# MyPi.net
KiCad netlist of a schematic drawn in EAGLE
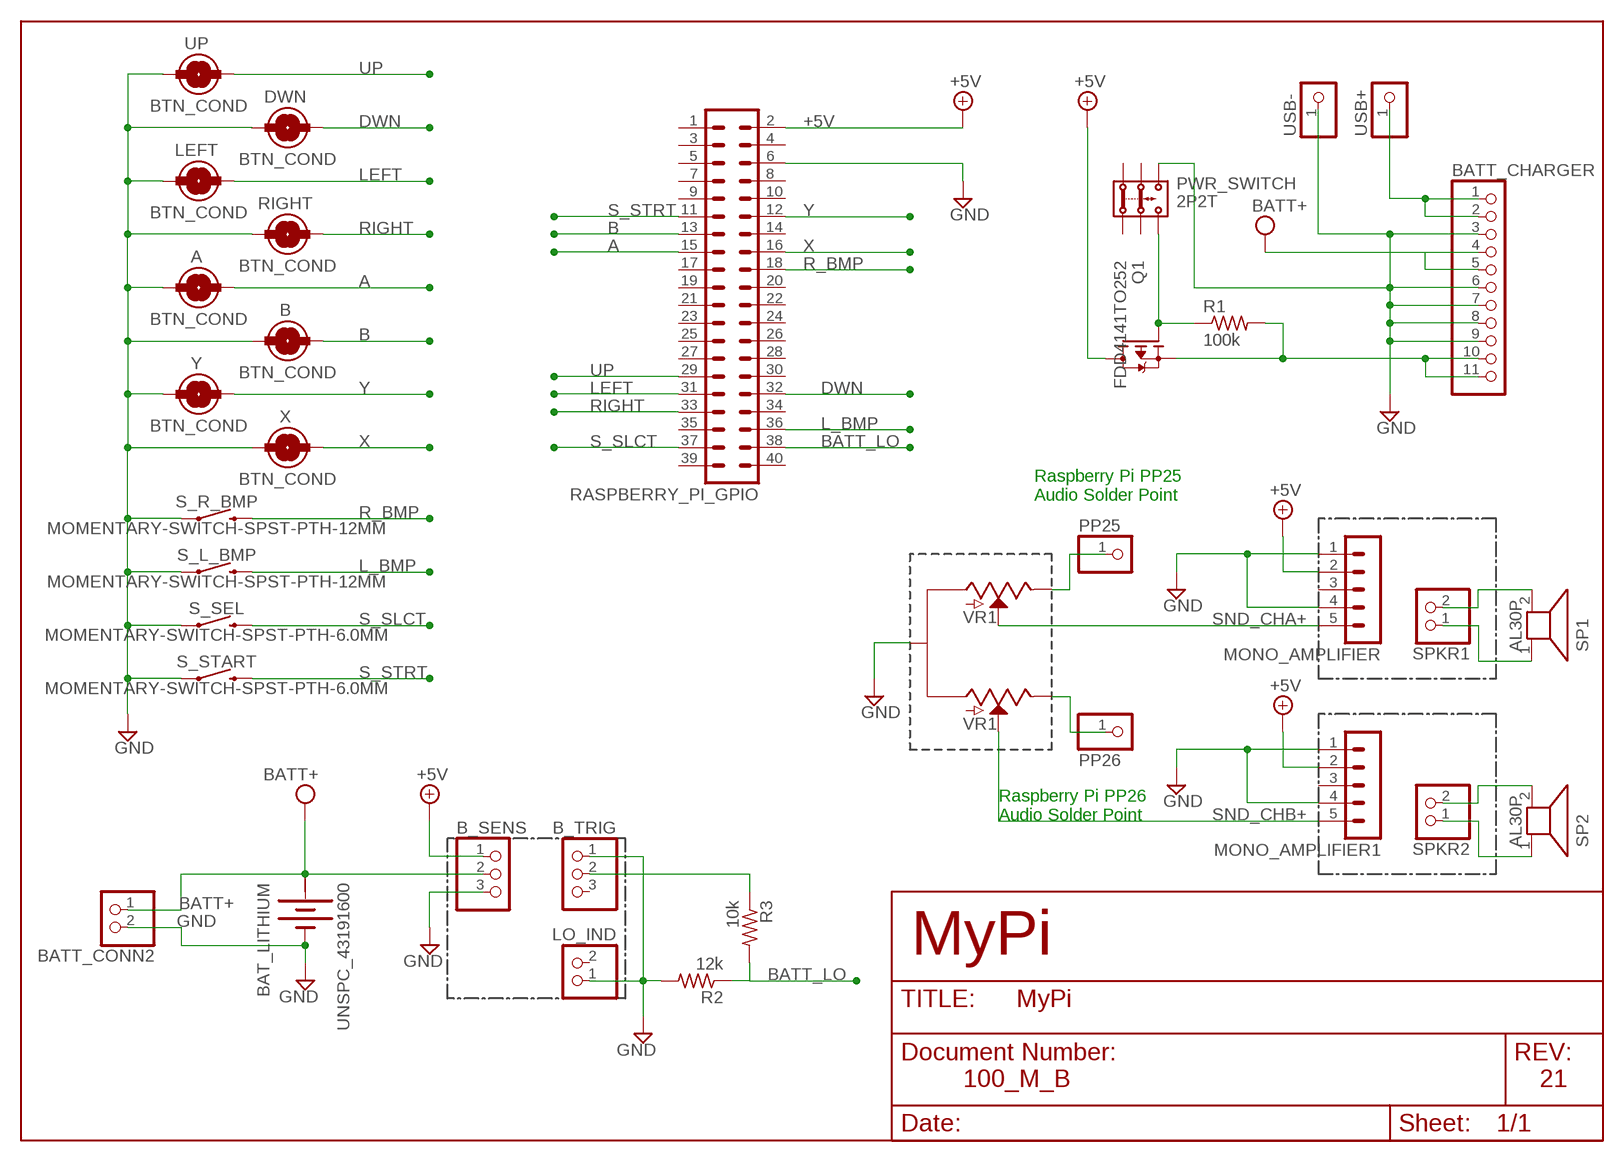
[diagram p0: schematic, sheet 1]

(export (version "E")
  (design (tool "Eeschema 10.0.6"))
  (components
    (comp (ref "A")
      (value "BTN_COND")
      (footprint "eagle-import:BUTTON-CONDUCTIVE-GC")
      (libsource (lib "eagle-import") (part "BTN_COND"))
    )
    (comp (ref "B")
      (value "BTN_COND")
      (footprint "eagle-import:BUTTON-CONDUCTIVE-GC")
      (libsource (lib "eagle-import") (part "BTN_COND"))
    )
    (comp (ref "BATT_CHARGER")
      (value "PINHD-1X11")
      (footprint "eagle-import:1X11")
      (libsource (lib "eagle-import") (part "PINHD-1X11"))
    )
    (comp (ref "BATT_CONN2")
      (value "JST_2PIN-THM-RA")
      (footprint "eagle-import:JST-PH-2-THM-RA")
      (libsource (lib "eagle-import") (part "JST_2PIN-THM-RA"))
    )
    (comp (ref "BAT_LITHIUM")
      (value "UNSPC_43191600")
      (footprint "eagle-import:BATTERY")
      (libsource (lib "eagle-import") (part "BATTERY"))
    )
    (comp (ref "B_SENS")
      (value "PINHD-1X3")
      (footprint "eagle-import:1X03")
      (libsource (lib "eagle-import") (part "PINHD-1X3"))
    )
    (comp (ref "B_TRIG")
      (value "PINHD-1X3")
      (footprint "eagle-import:1X03")
      (libsource (lib "eagle-import") (part "PINHD-1X3"))
    )
    (comp (ref "DWN")
      (value "BTN_COND")
      (footprint "eagle-import:BUTTON-CONDUCTIVE-GC")
      (libsource (lib "eagle-import") (part "BTN_COND"))
    )
    (comp (ref "LEFT")
      (value "BTN_COND")
      (footprint "eagle-import:BUTTON-CONDUCTIVE-GC")
      (libsource (lib "eagle-import") (part "BTN_COND"))
    )
    (comp (ref "LO_IND")
      (value "JST_2PIN-THM-RA")
      (footprint "eagle-import:JST-PH-2-THM-RA")
      (libsource (lib "eagle-import") (part "JST_2PIN-THM-RA"))
    )
    (comp (ref "MONO_AMPLIFIER")
      (value "MA05-1")
      (footprint "eagle-import:MA05-1")
      (libsource (lib "eagle-import") (part "MA05-1"))
    )
    (comp (ref "MONO_AMPLIFIER1")
      (value "MA05-1")
      (footprint "eagle-import:MA05-1")
      (libsource (lib "eagle-import") (part "MA05-1"))
    )
    (comp (ref "PP25")
      (value "PINHD-1X1")
      (footprint "eagle-import:1X01")
      (libsource (lib "eagle-import") (part "PINHD-1X1"))
    )
    (comp (ref "PP26")
      (value "PINHD-1X1")
      (footprint "eagle-import:1X01")
      (libsource (lib "eagle-import") (part "PINHD-1X1"))
    )
    (comp (ref "PWR_SWITCH")
      (value "2P2T")
      (footprint "eagle-import:2P2T")
      (libsource (lib "eagle-import") (part "2P2T"))
    )
    (comp (ref "Q1")
      (value "FDD4141TO252")
      (footprint "eagle-import:TO252")
      (libsource (lib "eagle-import") (part "FDD4141TO252"))
    )
    (comp (ref "R1")
      (value "100k")
      (footprint "eagle-import:R2512")
      (libsource (lib "eagle-import") (part "R-US_R2512"))
    )
    (comp (ref "R2")
      (value "12k")
      (footprint "eagle-import:R2512")
      (libsource (lib "eagle-import") (part "R-US_R2512"))
    )
    (comp (ref "R3")
      (value "10k")
      (footprint "eagle-import:R2512")
      (libsource (lib "eagle-import") (part "R-US_R2512"))
    )
    (comp (ref "RASPBERRY_PI_GPIO")
      (value "MA20-2")
      (footprint "eagle-import:MA20-2")
      (libsource (lib "eagle-import") (part "MA20-2"))
    )
    (comp (ref "RIGHT")
      (value "BTN_COND")
      (footprint "eagle-import:BUTTON-CONDUCTIVE-GC")
      (libsource (lib "eagle-import") (part "BTN_COND"))
    )
    (comp (ref "SP1")
      (value "AL30P")
      (footprint "eagle-import:AL30P")
      (libsource (lib "eagle-import") (part "AL30P"))
    )
    (comp (ref "SP2")
      (value "AL30P")
      (footprint "eagle-import:AL30P")
      (libsource (lib "eagle-import") (part "AL30P"))
    )
    (comp (ref "SPKR1")
      (value "PINHD-1X2")
      (footprint "eagle-import:1X02")
      (libsource (lib "eagle-import") (part "PINHD-1X2"))
    )
    (comp (ref "SPKR2")
      (value "PINHD-1X2")
      (footprint "eagle-import:1X02")
      (libsource (lib "eagle-import") (part "PINHD-1X2"))
    )
    (comp (ref "S_L_BMP")
      (value "MOMENTARY-SWITCH-SPST-PTH-12MM")
      (footprint "eagle-import:TACTILE_SWITCH_PTH_12MM")
      (libsource (lib "eagle-import") (part "MOMENTARY-SWITCH-SPST-PTH-12MM"))
    )
    (comp (ref "S_R_BMP")
      (value "MOMENTARY-SWITCH-SPST-PTH-12MM")
      (footprint "eagle-import:TACTILE_SWITCH_PTH_12MM")
      (libsource (lib "eagle-import") (part "MOMENTARY-SWITCH-SPST-PTH-12MM"))
    )
    (comp (ref "S_SEL")
      (value "MOMENTARY-SWITCH-SPST-PTH-6.0MM")
      (footprint "eagle-import:TACTILE_SWITCH_PTH_6.0MM")
      (libsource (lib "eagle-import") (part "MOMENTARY-SWITCH-SPST-PTH-6.0MM"))
    )
    (comp (ref "S_START")
      (value "MOMENTARY-SWITCH-SPST-PTH-6.0MM")
      (footprint "eagle-import:TACTILE_SWITCH_PTH_6.0MM")
      (libsource (lib "eagle-import") (part "MOMENTARY-SWITCH-SPST-PTH-6.0MM"))
    )
    (comp (ref "UP")
      (value "BTN_COND")
      (footprint "eagle-import:BUTTON-CONDUCTIVE-GC")
      (libsource (lib "eagle-import") (part "BTN_COND"))
    )
    (comp (ref "USB+")
      (value "PINHD-1X1")
      (footprint "eagle-import:1X01")
      (libsource (lib "eagle-import") (part "PINHD-1X1"))
    )
    (comp (ref "USB-")
      (value "PINHD-1X1")
      (footprint "eagle-import:1X01")
      (libsource (lib "eagle-import") (part "PINHD-1X1"))
    )
    (comp (ref "VR1")
      (value "POTENTIOMETER_DUAL-PTH-12MM-1/20W-20%")
      (footprint "eagle-import:POT-DUAL-PTH-UXCELL")
      (libsource (lib "eagle-import") (part "POTENTIOMETER_DUAL-PTH-12MM-1/20W-20%"))
    )
    (comp (ref "X")
      (value "BTN_COND")
      (footprint "eagle-import:BUTTON-CONDUCTIVE-GC")
      (libsource (lib "eagle-import") (part "BTN_COND"))
    )
    (comp (ref "Y")
      (value "BTN_COND")
      (footprint "eagle-import:BUTTON-CONDUCTIVE-GC")
      (libsource (lib "eagle-import") (part "BTN_COND"))
    )
  )
  (nets
    (net (code "1") (name "+5V") (class "Default")
      (node (ref "B_SENS") (pin "1") (pinfunction "1_1") (pintype "passive"))
      (node (ref "MONO_AMPLIFIER") (pin "2") (pinfunction "2_2") (pintype "passive"))
      (node (ref "MONO_AMPLIFIER1") (pin "2") (pinfunction "2_2") (pintype "passive"))
      (node (ref "Q1") (pin "3") (pinfunction "D_3") (pintype "passive"))
      (node (ref "RASPBERRY_PI_GPIO") (pin "2") (pinfunction "2_2") (pintype "passive"))
    )
    (net (code "2") (name "/+") (class "Default")
      (node (ref "BAT_LITHIUM") (pin "+@1") (pinfunction "+_+@1") (pintype "power_in"))
    )
    (net (code "3") (name "/A") (class "Default")
      (node (ref "A") (pin "2") (pinfunction "2_2") (pintype "passive"))
      (node (ref "RASPBERRY_PI_GPIO") (pin "15") (pinfunction "15_15") (pintype "passive"))
    )
    (net (code "4") (name "/B") (class "Default")
      (node (ref "B") (pin "2") (pinfunction "2_2") (pintype "passive"))
      (node (ref "RASPBERRY_PI_GPIO") (pin "13") (pinfunction "13_13") (pintype "passive"))
    )
    (net (code "5") (name "/BATT_LO") (class "Default")
      (node (ref "R2") (pin "1") (pinfunction "1_1") (pintype "passive"))
      (node (ref "R3") (pin "2") (pinfunction "2_2") (pintype "passive"))
      (node (ref "RASPBERRY_PI_GPIO") (pin "38") (pinfunction "38_38") (pintype "passive"))
    )
    (net (code "6") (name "/DWN") (class "Default")
      (node (ref "DWN") (pin "2") (pinfunction "2_2") (pintype "passive"))
      (node (ref "RASPBERRY_PI_GPIO") (pin "32") (pinfunction "32_32") (pintype "passive"))
    )
    (net (code "7") (name "/LEFT") (class "Default")
      (node (ref "LEFT") (pin "2") (pinfunction "2_2") (pintype "passive"))
      (node (ref "RASPBERRY_PI_GPIO") (pin "31") (pinfunction "31_31") (pintype "passive"))
    )
    (net (code "8") (name "/L_BMP") (class "Default")
      (node (ref "RASPBERRY_PI_GPIO") (pin "36") (pinfunction "36_36") (pintype "passive"))
      (node (ref "S_L_BMP") (pin "3") (pinfunction "2_3") (pintype "passive"))
    )
    (net (code "9") (name "/RIGHT") (class "Default")
      (node (ref "RASPBERRY_PI_GPIO") (pin "33") (pinfunction "33_33") (pintype "passive"))
      (node (ref "RIGHT") (pin "2") (pinfunction "2_2") (pintype "passive"))
    )
    (net (code "10") (name "/R_BMP") (class "Default")
      (node (ref "RASPBERRY_PI_GPIO") (pin "18") (pinfunction "18_18") (pintype "passive"))
      (node (ref "S_R_BMP") (pin "3") (pinfunction "2_3") (pintype "passive"))
    )
    (net (code "11") (name "/SND_CHA+") (class "Default")
      (node (ref "MONO_AMPLIFIER") (pin "5") (pinfunction "5_5") (pintype "passive"))
      (node (ref "VR1") (pin "A_OUT") (pinfunction "A_OUT_A_OUT") (pintype "passive"))
    )
    (net (code "12") (name "/SND_CHB+") (class "Default")
      (node (ref "MONO_AMPLIFIER1") (pin "5") (pinfunction "5_5") (pintype "passive"))
      (node (ref "VR1") (pin "B_OUT") (pinfunction "B_OUT_B_OUT") (pintype "passive"))
    )
    (net (code "13") (name "/S_SLCT") (class "Default")
      (node (ref "RASPBERRY_PI_GPIO") (pin "37") (pinfunction "37_37") (pintype "passive"))
      (node (ref "S_SEL") (pin "3") (pinfunction "2_3") (pintype "passive"))
    )
    (net (code "14") (name "/S_STRT") (class "Default")
      (node (ref "RASPBERRY_PI_GPIO") (pin "11") (pinfunction "11_11") (pintype "passive"))
      (node (ref "S_START") (pin "3") (pinfunction "2_3") (pintype "passive"))
    )
    (net (code "15") (name "/UP") (class "Default")
      (node (ref "RASPBERRY_PI_GPIO") (pin "29") (pinfunction "29_29") (pintype "passive"))
      (node (ref "UP") (pin "2") (pinfunction "2_2") (pintype "passive"))
    )
    (net (code "16") (name "/X") (class "Default")
      (node (ref "RASPBERRY_PI_GPIO") (pin "16") (pinfunction "16_16") (pintype "passive"))
      (node (ref "X") (pin "2") (pinfunction "2_2") (pintype "passive"))
    )
    (net (code "17") (name "/Y") (class "Default")
      (node (ref "RASPBERRY_PI_GPIO") (pin "12") (pinfunction "12_12") (pintype "passive"))
      (node (ref "Y") (pin "2") (pinfunction "2_2") (pintype "passive"))
    )
    (net (code "18") (name "BATT+") (class "Default")
      (node (ref "BATT_CHARGER") (pin "4") (pinfunction "4_4") (pintype "passive"))
      (node (ref "BATT_CHARGER") (pin "5") (pinfunction "5_5") (pintype "passive"))
      (node (ref "BATT_CONN2") (pin "1") (pinfunction "2_1") (pintype "passive"))
      (node (ref "BAT_LITHIUM") (pin "+") (pinfunction "+_+") (pintype "power_in"))
      (node (ref "B_SENS") (pin "2") (pinfunction "2_2") (pintype "passive"))
    )
    (net (code "19") (name "GND") (class "Default")
      (node (ref "A") (pin "1") (pinfunction "1_1") (pintype "passive"))
      (node (ref "B") (pin "1") (pinfunction "1_1") (pintype "passive"))
      (node (ref "BATT_CHARGER") (pin "3") (pinfunction "3_3") (pintype "passive"))
      (node (ref "BATT_CHARGER") (pin "6") (pinfunction "6_6") (pintype "passive"))
      (node (ref "BATT_CHARGER") (pin "7") (pinfunction "7_7") (pintype "passive"))
      (node (ref "BATT_CHARGER") (pin "8") (pinfunction "8_8") (pintype "passive"))
      (node (ref "BATT_CHARGER") (pin "9") (pinfunction "9_9") (pintype "passive"))
      (node (ref "BATT_CONN2") (pin "2") (pinfunction "1_2") (pintype "passive"))
      (node (ref "BAT_LITHIUM") (pin "-") (pinfunction "-_-") (pintype "power_in"))
      (node (ref "B_SENS") (pin "3") (pinfunction "3_3") (pintype "passive"))
      (node (ref "B_TRIG") (pin "1") (pinfunction "1_1") (pintype "passive"))
      (node (ref "DWN") (pin "1") (pinfunction "1_1") (pintype "passive"))
      (node (ref "LEFT") (pin "1") (pinfunction "1_1") (pintype "passive"))
      (node (ref "LO_IND") (pin "1") (pinfunction "2_1") (pintype "passive"))
      (node (ref "MONO_AMPLIFIER") (pin "1") (pinfunction "1_1") (pintype "passive"))
      (node (ref "MONO_AMPLIFIER") (pin "4") (pinfunction "4_4") (pintype "passive"))
      (node (ref "MONO_AMPLIFIER1") (pin "1") (pinfunction "1_1") (pintype "passive"))
      (node (ref "MONO_AMPLIFIER1") (pin "4") (pinfunction "4_4") (pintype "passive"))
      (node (ref "PWR_SWITCH") (pin "3.1") (pinfunction "3.1_3.1") (pintype "passive"))
      (node (ref "R2") (pin "2") (pinfunction "2_2") (pintype "passive"))
      (node (ref "RASPBERRY_PI_GPIO") (pin "6") (pinfunction "6_6") (pintype "passive"))
      (node (ref "RIGHT") (pin "1") (pinfunction "1_1") (pintype "passive"))
      (node (ref "S_L_BMP") (pin "1") (pinfunction "1_1") (pintype "passive"))
      (node (ref "S_R_BMP") (pin "1") (pinfunction "1_1") (pintype "passive"))
      (node (ref "S_SEL") (pin "1") (pinfunction "1_1") (pintype "passive"))
      (node (ref "S_START") (pin "1") (pinfunction "1_1") (pintype "passive"))
      (node (ref "UP") (pin "1") (pinfunction "1_1") (pintype "passive"))
      (node (ref "USB-") (pin "1") (pinfunction "1_1") (pintype "passive"))
      (node (ref "VR1") (pin "COM") (pinfunction "A_COM") (pintype "passive"))
      (node (ref "X") (pin "1") (pinfunction "1_1") (pintype "passive"))
      (node (ref "Y") (pin "1") (pinfunction "1_1") (pintype "passive"))
    )
    (net (code "20") (name "Net-(BATT_CHARGER-Pad1)") (class "Default")
      (node (ref "BATT_CHARGER") (pin "1") (pinfunction "1_1") (pintype "passive"))
      (node (ref "BATT_CHARGER") (pin "2") (pinfunction "2_2") (pintype "passive"))
      (node (ref "USB+") (pin "1") (pinfunction "1_1") (pintype "passive"))
    )
    (net (code "21") (name "Net-(B_TRIG-Pad2)") (class "Default")
      (node (ref "B_TRIG") (pin "2") (pinfunction "2_2") (pintype "passive"))
      (node (ref "R3") (pin "1") (pinfunction "1_1") (pintype "passive"))
    )
    (net (code "22") (name "Net-(PP25-Pad1)") (class "Default")
      (node (ref "PP25") (pin "1") (pinfunction "1_1") (pintype "passive"))
      (node (ref "VR1") (pin "A_IN") (pinfunction "A_IN_A_IN") (pintype "passive"))
    )
    (net (code "23") (name "Net-(PP26-Pad1)") (class "Default")
      (node (ref "PP26") (pin "1") (pinfunction "1_1") (pintype "passive"))
      (node (ref "VR1") (pin "B_IN") (pinfunction "B_IN_B_IN") (pintype "passive"))
    )
    (net (code "24") (name "Net-(Q1-G)") (class "Default")
      (node (ref "PWR_SWITCH") (pin "3.2") (pinfunction "3.2_3.2") (pintype "passive"))
      (node (ref "Q1") (pin "1") (pinfunction "G_1") (pintype "passive"))
      (node (ref "R1") (pin "1") (pinfunction "1_1") (pintype "passive"))
    )
    (net (code "25") (name "Net-(Q1-S)") (class "Default")
      (node (ref "BATT_CHARGER") (pin "10") (pinfunction "10_10") (pintype "passive"))
      (node (ref "BATT_CHARGER") (pin "11") (pinfunction "11_11") (pintype "passive"))
      (node (ref "Q1") (pin "2") (pinfunction "S_2") (pintype "passive"))
      (node (ref "R1") (pin "2") (pinfunction "2_2") (pintype "passive"))
    )
    (net (code "26") (name "Net-(SP1-Pad1)") (class "Default")
      (node (ref "SP1") (pin "1") (pinfunction "1_1") (pintype "passive"))
      (node (ref "SPKR1") (pin "1") (pinfunction "1_1") (pintype "passive"))
    )
    (net (code "27") (name "Net-(SP1-Pad2)") (class "Default")
      (node (ref "SP1") (pin "2") (pinfunction "2_2") (pintype "passive"))
      (node (ref "SPKR1") (pin "2") (pinfunction "2_2") (pintype "passive"))
    )
    (net (code "28") (name "Net-(SP2-Pad1)") (class "Default")
      (node (ref "SP2") (pin "1") (pinfunction "1_1") (pintype "passive"))
      (node (ref "SPKR2") (pin "1") (pinfunction "1_1") (pintype "passive"))
    )
    (net (code "29") (name "Net-(SP2-Pad2)") (class "Default")
      (node (ref "SP2") (pin "2") (pinfunction "2_2") (pintype "passive"))
      (node (ref "SPKR2") (pin "2") (pinfunction "2_2") (pintype "passive"))
    )
    (net (code "30") (name "unconnected-(B_TRIG-Pad3)") (class "Default")
      (node (ref "B_TRIG") (pin "3") (pinfunction "3_3") (pintype "passive"))
    )
    (net (code "31") (name "unconnected-(LO_IND-1-Pad2)") (class "Default")
      (node (ref "LO_IND") (pin "2") (pinfunction "1_2") (pintype "passive"))
    )
    (net (code "32") (name "unconnected-(MONO_AMPLIFIER-Pad3)") (class "Default")
      (node (ref "MONO_AMPLIFIER") (pin "3") (pinfunction "3_3") (pintype "passive"))
    )
    (net (code "33") (name "unconnected-(MONO_AMPLIFIER1-Pad3)") (class "Default")
      (node (ref "MONO_AMPLIFIER1") (pin "3") (pinfunction "3_3") (pintype "passive"))
    )
    (net (code "34") (name "unconnected-(PWR_SWITCH-Pad1.1)") (class "Default")
      (node (ref "PWR_SWITCH") (pin "1.1") (pinfunction "1.1_1.1") (pintype "passive"))
    )
    (net (code "35") (name "unconnected-(PWR_SWITCH-Pad1.2)") (class "Default")
      (node (ref "PWR_SWITCH") (pin "1.2") (pinfunction "1.2_1.2") (pintype "passive"))
    )
    (net (code "36") (name "unconnected-(PWR_SWITCH-Pad2.1)") (class "Default")
      (node (ref "PWR_SWITCH") (pin "2.1") (pinfunction "2.1_2.1") (pintype "passive"))
    )
    (net (code "37") (name "unconnected-(PWR_SWITCH-Pad2.2)") (class "Default")
      (node (ref "PWR_SWITCH") (pin "2.2") (pinfunction "2.2_2.2") (pintype "passive"))
    )
    (net (code "38") (name "unconnected-(RASPBERRY_PI_GPIO-Pad1)") (class "Default")
      (node (ref "RASPBERRY_PI_GPIO") (pin "1") (pinfunction "1_1") (pintype "passive"))
    )
    (net (code "39") (name "unconnected-(RASPBERRY_PI_GPIO-Pad3)") (class "Default")
      (node (ref "RASPBERRY_PI_GPIO") (pin "3") (pinfunction "3_3") (pintype "passive"))
    )
    (net (code "40") (name "unconnected-(RASPBERRY_PI_GPIO-Pad4)") (class "Default")
      (node (ref "RASPBERRY_PI_GPIO") (pin "4") (pinfunction "4_4") (pintype "passive"))
    )
    (net (code "41") (name "unconnected-(RASPBERRY_PI_GPIO-Pad5)") (class "Default")
      (node (ref "RASPBERRY_PI_GPIO") (pin "5") (pinfunction "5_5") (pintype "passive"))
    )
    (net (code "42") (name "unconnected-(RASPBERRY_PI_GPIO-Pad7)") (class "Default")
      (node (ref "RASPBERRY_PI_GPIO") (pin "7") (pinfunction "7_7") (pintype "passive"))
    )
    (net (code "43") (name "unconnected-(RASPBERRY_PI_GPIO-Pad8)") (class "Default")
      (node (ref "RASPBERRY_PI_GPIO") (pin "8") (pinfunction "8_8") (pintype "passive"))
    )
    (net (code "44") (name "unconnected-(RASPBERRY_PI_GPIO-Pad9)") (class "Default")
      (node (ref "RASPBERRY_PI_GPIO") (pin "9") (pinfunction "9_9") (pintype "passive"))
    )
    (net (code "45") (name "unconnected-(RASPBERRY_PI_GPIO-Pad10)") (class "Default")
      (node (ref "RASPBERRY_PI_GPIO") (pin "10") (pinfunction "10_10") (pintype "passive"))
    )
    (net (code "46") (name "unconnected-(RASPBERRY_PI_GPIO-Pad14)") (class "Default")
      (node (ref "RASPBERRY_PI_GPIO") (pin "14") (pinfunction "14_14") (pintype "passive"))
    )
    (net (code "47") (name "unconnected-(RASPBERRY_PI_GPIO-Pad17)") (class "Default")
      (node (ref "RASPBERRY_PI_GPIO") (pin "17") (pinfunction "17_17") (pintype "passive"))
    )
    (net (code "48") (name "unconnected-(RASPBERRY_PI_GPIO-Pad19)") (class "Default")
      (node (ref "RASPBERRY_PI_GPIO") (pin "19") (pinfunction "19_19") (pintype "passive"))
    )
    (net (code "49") (name "unconnected-(RASPBERRY_PI_GPIO-Pad20)") (class "Default")
      (node (ref "RASPBERRY_PI_GPIO") (pin "20") (pinfunction "20_20") (pintype "passive"))
    )
    (net (code "50") (name "unconnected-(RASPBERRY_PI_GPIO-Pad21)") (class "Default")
      (node (ref "RASPBERRY_PI_GPIO") (pin "21") (pinfunction "21_21") (pintype "passive"))
    )
    (net (code "51") (name "unconnected-(RASPBERRY_PI_GPIO-Pad22)") (class "Default")
      (node (ref "RASPBERRY_PI_GPIO") (pin "22") (pinfunction "22_22") (pintype "passive"))
    )
    (net (code "52") (name "unconnected-(RASPBERRY_PI_GPIO-Pad23)") (class "Default")
      (node (ref "RASPBERRY_PI_GPIO") (pin "23") (pinfunction "23_23") (pintype "passive"))
    )
    (net (code "53") (name "unconnected-(RASPBERRY_PI_GPIO-Pad24)") (class "Default")
      (node (ref "RASPBERRY_PI_GPIO") (pin "24") (pinfunction "24_24") (pintype "passive"))
    )
    (net (code "54") (name "unconnected-(RASPBERRY_PI_GPIO-Pad25)") (class "Default")
      (node (ref "RASPBERRY_PI_GPIO") (pin "25") (pinfunction "25_25") (pintype "passive"))
    )
    (net (code "55") (name "unconnected-(RASPBERRY_PI_GPIO-Pad26)") (class "Default")
      (node (ref "RASPBERRY_PI_GPIO") (pin "26") (pinfunction "26_26") (pintype "passive"))
    )
    (net (code "56") (name "unconnected-(RASPBERRY_PI_GPIO-Pad27)") (class "Default")
      (node (ref "RASPBERRY_PI_GPIO") (pin "27") (pinfunction "27_27") (pintype "passive"))
    )
    (net (code "57") (name "unconnected-(RASPBERRY_PI_GPIO-Pad28)") (class "Default")
      (node (ref "RASPBERRY_PI_GPIO") (pin "28") (pinfunction "28_28") (pintype "passive"))
    )
    (net (code "58") (name "unconnected-(RASPBERRY_PI_GPIO-Pad30)") (class "Default")
      (node (ref "RASPBERRY_PI_GPIO") (pin "30") (pinfunction "30_30") (pintype "passive"))
    )
    (net (code "59") (name "unconnected-(RASPBERRY_PI_GPIO-Pad34)") (class "Default")
      (node (ref "RASPBERRY_PI_GPIO") (pin "34") (pinfunction "34_34") (pintype "passive"))
    )
    (net (code "60") (name "unconnected-(RASPBERRY_PI_GPIO-Pad35)") (class "Default")
      (node (ref "RASPBERRY_PI_GPIO") (pin "35") (pinfunction "35_35") (pintype "passive"))
    )
    (net (code "61") (name "unconnected-(RASPBERRY_PI_GPIO-Pad39)") (class "Default")
      (node (ref "RASPBERRY_PI_GPIO") (pin "39") (pinfunction "39_39") (pintype "passive"))
    )
    (net (code "62") (name "unconnected-(RASPBERRY_PI_GPIO-Pad40)") (class "Default")
      (node (ref "RASPBERRY_PI_GPIO") (pin "40") (pinfunction "40_40") (pintype "passive"))
    )
  )
)
